# follower_2015-3.net
KiCad netlist of a schematic drawn in EAGLE
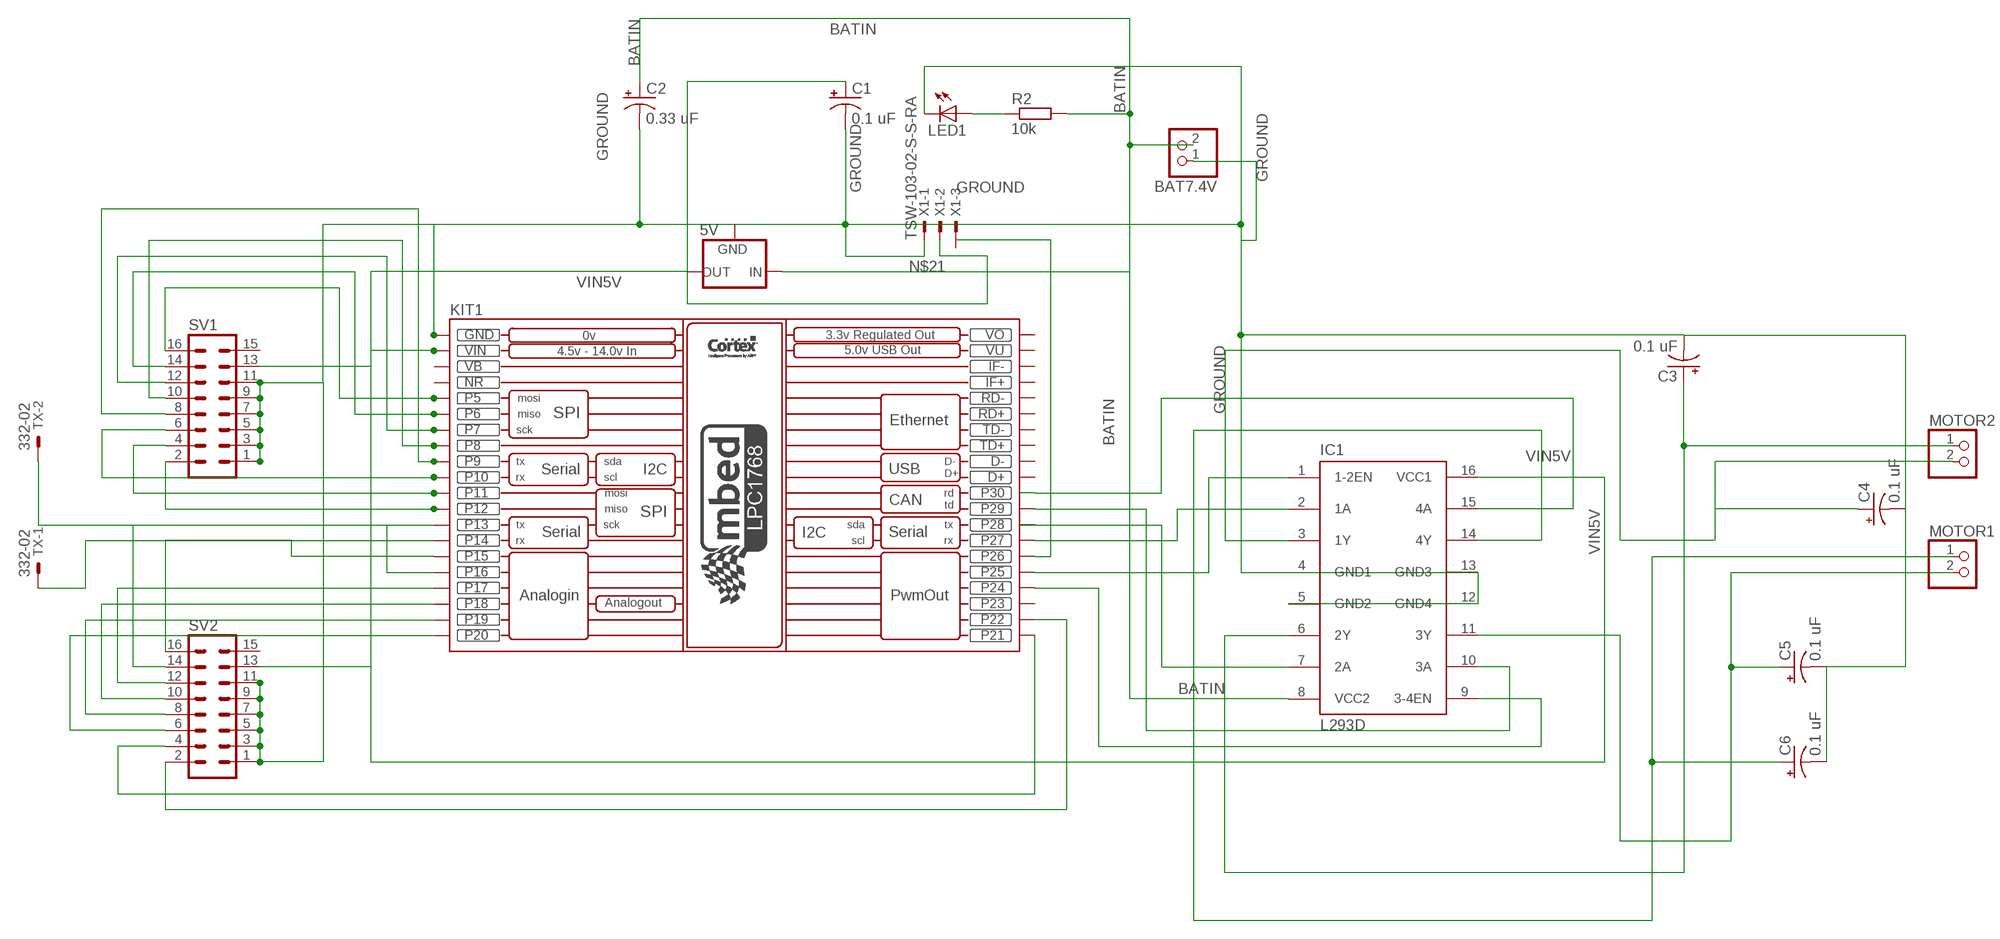
[diagram p0: schematic, sheet 1]

(export (version "E")
  (design (tool "Eeschema 10.0.6"))
  (components
    (comp (ref "5V")
      (value "78XXL")
      (footprint "eagle-import:78XXL")
      (libsource (lib "eagle-import") (part "78XXL"))
    )
    (comp (ref "BAT7.4V")
      (value "PINHD-1X2")
      (footprint "eagle-import:1X02")
      (libsource (lib "eagle-import") (part "PINHD-1X2"))
    )
    (comp (ref "C1")
      (value "0.1 uF")
      (footprint "eagle-import:TT5D6")
      (libsource (lib "eagle-import") (part "CPOL-USTT6D6"))
    )
    (comp (ref "C2")
      (value "0.33 uF")
      (footprint "eagle-import:TT5D6")
      (libsource (lib "eagle-import") (part "CPOL-USTT6D6"))
    )
    (comp (ref "C3")
      (value "0.1 uF")
      (footprint "eagle-import:TT5D6")
      (libsource (lib "eagle-import") (part "CPOL-USTT6D6"))
    )
    (comp (ref "C4")
      (value "0.1 uF")
      (footprint "eagle-import:TT5D6")
      (libsource (lib "eagle-import") (part "CPOL-USTT6D6"))
    )
    (comp (ref "C5")
      (value "0.1 uF")
      (footprint "eagle-import:TT5D6")
      (libsource (lib "eagle-import") (part "CPOL-USTT6D6"))
    )
    (comp (ref "C6")
      (value "0.1 uF")
      (footprint "eagle-import:TT5D6")
      (libsource (lib "eagle-import") (part "CPOL-USTT6D6"))
    )
    (comp (ref "IC1")
      (value "L293D")
      (footprint "eagle-import:DIL16")
      (libsource (lib "eagle-import") (part "L293D"))
    )
    (comp (ref "KIT1")
      (value "MBED_NXP_LPC1768")
      (footprint "eagle-import:MBED-KIT")
      (libsource (lib "eagle-import") (part "MBED_NXP_LPC1768"))
    )
    (comp (ref "LED1")
      (value "LED3MM")
      (footprint "eagle-import:LED3MM")
      (libsource (lib "eagle-import") (part "LED3MM"))
    )
    (comp (ref "MOTOR1")
      (value "PINHD-1X2")
      (footprint "eagle-import:1X02")
      (libsource (lib "eagle-import") (part "PINHD-1X2"))
    )
    (comp (ref "MOTOR2")
      (value "PINHD-1X2")
      (footprint "eagle-import:1X02")
      (libsource (lib "eagle-import") (part "PINHD-1X2"))
    )
    (comp (ref "R2")
      (value "10k")
      (footprint "eagle-import:0204_5")
      (libsource (lib "eagle-import") (part "R-EU_0204/5"))
    )
    (comp (ref "SV1")
      (value "MA08-2")
      (footprint "eagle-import:MA08-2")
      (libsource (lib "eagle-import") (part "MA08-2"))
    )
    (comp (ref "SV2")
      (value "MA08-2")
      (footprint "eagle-import:MA08-2")
      (libsource (lib "eagle-import") (part "MA08-2"))
    )
    (comp (ref "TX")
      (value "332-02")
      (footprint "eagle-import:332-02")
      (libsource (lib "eagle-import") (part "332-02"))
    )
    (comp (ref "X1")
      (value "TSW-103-02-S-S-RA")
      (footprint "eagle-import:TSW-103-02-S-S-RA")
      (libsource (lib "eagle-import") (part "TSW-103-02-S-S-RA"))
    )
  )
  (nets
    (net (code "1") (name "/BATIN") (class "Default")
      (node (ref "BAT7.4V") (pin "2") (pinfunction "2_2") (pintype "passive"))
      (node (ref "C2") (pin "+") (pinfunction "+_+") (pintype "passive"))
      (node (ref "IC1") (pin "8") (pinfunction "VCC2_8") (pintype "power_in"))
      (node (ref "R2") (pin "2") (pinfunction "2_2") (pintype "passive"))
    )
    (net (code "2") (name "/GROUND") (class "Default")
      (node (ref "5V") (pin "GND") (pinfunction "GND_GND") (pintype "input"))
      (node (ref "BAT7.4V") (pin "1") (pinfunction "1_1") (pintype "passive"))
      (node (ref "C1") (pin "-") (pinfunction "-_-") (pintype "passive"))
      (node (ref "C2") (pin "-") (pinfunction "-_-") (pintype "passive"))
      (node (ref "C3") (pin "-") (pinfunction "-_-") (pintype "passive"))
      (node (ref "C4") (pin "-") (pinfunction "-_-") (pintype "passive"))
      (node (ref "C5") (pin "-") (pinfunction "-_-") (pintype "passive"))
      (node (ref "C6") (pin "-") (pinfunction "-_-") (pintype "passive"))
      (node (ref "IC1") (pin "12") (pinfunction "GND4_12") (pintype "power_in"))
      (node (ref "IC1") (pin "13") (pinfunction "GND3_13") (pintype "power_in"))
      (node (ref "IC1") (pin "4") (pinfunction "GND1_4") (pintype "power_in"))
      (node (ref "IC1") (pin "5") (pinfunction "GND2_5") (pintype "power_in"))
      (node (ref "KIT1") (pin "GND") (pinfunction "GND_GND") (pintype "power_in"))
      (node (ref "LED1") (pin "K") (pinfunction "C_K") (pintype "passive"))
      (node (ref "SV1") (pin "1") (pinfunction "1_1") (pintype "passive"))
      (node (ref "SV1") (pin "11") (pinfunction "11_11") (pintype "passive"))
      (node (ref "SV1") (pin "3") (pinfunction "3_3") (pintype "passive"))
      (node (ref "SV1") (pin "5") (pinfunction "5_5") (pintype "passive"))
      (node (ref "SV1") (pin "7") (pinfunction "7_7") (pintype "passive"))
      (node (ref "SV1") (pin "9") (pinfunction "9_9") (pintype "passive"))
      (node (ref "SV2") (pin "1") (pinfunction "1_1") (pintype "passive"))
      (node (ref "SV2") (pin "11") (pinfunction "11_11") (pintype "passive"))
      (node (ref "SV2") (pin "3") (pinfunction "3_3") (pintype "passive"))
      (node (ref "SV2") (pin "5") (pinfunction "5_5") (pintype "passive"))
      (node (ref "SV2") (pin "7") (pinfunction "7_7") (pintype "passive"))
      (node (ref "SV2") (pin "9") (pinfunction "9_9") (pintype "passive"))
    )
    (net (code "3") (name "/N$21") (class "Default")
      (node (ref "5V") (pin "IN") (pinfunction "IN_IN") (pintype "input"))
    )
    (net (code "4") (name "/NR") (class "Default")
      (node (ref "KIT1") (pin "NR") (pinfunction "NR_NR") (pintype "power_in"))
    )
    (net (code "5") (name "/VB") (class "Default")
      (node (ref "KIT1") (pin "VB") (pinfunction "VB_VB") (pintype "power_in"))
    )
    (net (code "6") (name "/VIN5V") (class "Default")
      (node (ref "5V") (pin "OUT") (pinfunction "OUT_OUT") (pintype "passive"))
      (node (ref "C1") (pin "+") (pinfunction "+_+") (pintype "passive"))
      (node (ref "IC1") (pin "16") (pinfunction "VCC1_16") (pintype "power_in"))
      (node (ref "KIT1") (pin "VIN") (pinfunction "VIN_VIN") (pintype "power_in"))
      (node (ref "SV1") (pin "13") (pinfunction "13_13") (pintype "passive"))
      (node (ref "SV2") (pin "13") (pinfunction "13_13") (pintype "passive"))
    )
    (net (code "7") (name "/VO") (class "Default")
      (node (ref "KIT1") (pin "VOUT") (pinfunction "VO_VOUT") (pintype "power_in"))
    )
    (net (code "8") (name "/VU") (class "Default")
      (node (ref "KIT1") (pin "VU") (pinfunction "VU_VU") (pintype "power_in"))
    )
    (net (code "9") (name "Net-(IC1-1-2EN)") (class "Default")
      (node (ref "IC1") (pin "1") (pinfunction "1-2EN_1") (pintype "input"))
      (node (ref "KIT1") (pin "P$25") (pinfunction "P25_P$25") (pintype "bidirectional"))
    )
    (net (code "10") (name "Net-(IC1-1A)") (class "Default")
      (node (ref "IC1") (pin "2") (pinfunction "1A_2") (pintype "input"))
      (node (ref "KIT1") (pin "P$27") (pinfunction "P27_P$27") (pintype "bidirectional"))
    )
    (net (code "11") (name "Net-(IC1-1Y)") (class "Default")
      (node (ref "C4") (pin "+") (pinfunction "+_+") (pintype "passive"))
      (node (ref "IC1") (pin "3") (pinfunction "1Y_3") (pintype "output"))
      (node (ref "MOTOR2") (pin "2") (pinfunction "2_2") (pintype "passive"))
    )
    (net (code "12") (name "Net-(IC1-2Y)") (class "Default")
      (node (ref "C3") (pin "+") (pinfunction "+_+") (pintype "passive"))
      (node (ref "IC1") (pin "6") (pinfunction "2Y_6") (pintype "output"))
      (node (ref "MOTOR2") (pin "1") (pinfunction "1_1") (pintype "passive"))
    )
    (net (code "13") (name "Net-(IC1-3-4EN)") (class "Default")
      (node (ref "IC1") (pin "9") (pinfunction "3-4EN_9") (pintype "input"))
      (node (ref "KIT1") (pin "P$24") (pinfunction "P24_P$24") (pintype "bidirectional"))
    )
    (net (code "14") (name "Net-(IC1-3A)") (class "Default")
      (node (ref "IC1") (pin "10") (pinfunction "3A_10") (pintype "input"))
      (node (ref "KIT1") (pin "P$29") (pinfunction "P29_P$29") (pintype "bidirectional"))
    )
    (net (code "15") (name "Net-(IC1-3Y)") (class "Default")
      (node (ref "C5") (pin "+") (pinfunction "+_+") (pintype "passive"))
      (node (ref "IC1") (pin "11") (pinfunction "3Y_11") (pintype "output"))
      (node (ref "MOTOR1") (pin "2") (pinfunction "2_2") (pintype "passive"))
    )
    (net (code "16") (name "Net-(IC1-4A)") (class "Default")
      (node (ref "IC1") (pin "15") (pinfunction "4A_15") (pintype "input"))
      (node (ref "KIT1") (pin "P$30") (pinfunction "P30_P$30") (pintype "bidirectional"))
    )
    (net (code "17") (name "Net-(IC1-4Y)") (class "Default")
      (node (ref "C6") (pin "+") (pinfunction "+_+") (pintype "passive"))
      (node (ref "IC1") (pin "14") (pinfunction "4Y_14") (pintype "output"))
      (node (ref "MOTOR1") (pin "1") (pinfunction "1_1") (pintype "passive"))
    )
    (net (code "18") (name "Net-(KIT1-P5)") (class "Default")
      (node (ref "KIT1") (pin "P$5") (pinfunction "P5_P$5") (pintype "bidirectional"))
      (node (ref "SV1") (pin "16") (pinfunction "16_16") (pintype "passive"))
    )
    (net (code "19") (name "Net-(KIT1-P6)") (class "Default")
      (node (ref "KIT1") (pin "P$6") (pinfunction "P6_P$6") (pintype "bidirectional"))
      (node (ref "SV1") (pin "14") (pinfunction "14_14") (pintype "passive"))
    )
    (net (code "20") (name "Net-(KIT1-P7)") (class "Default")
      (node (ref "KIT1") (pin "P$7") (pinfunction "P7_P$7") (pintype "bidirectional"))
      (node (ref "SV1") (pin "12") (pinfunction "12_12") (pintype "passive"))
    )
    (net (code "21") (name "Net-(KIT1-P8)") (class "Default")
      (node (ref "KIT1") (pin "P$8") (pinfunction "P8_P$8") (pintype "bidirectional"))
      (node (ref "SV1") (pin "10") (pinfunction "10_10") (pintype "passive"))
    )
    (net (code "22") (name "Net-(KIT1-P9)") (class "Default")
      (node (ref "KIT1") (pin "P$9") (pinfunction "P9_P$9") (pintype "bidirectional"))
      (node (ref "SV1") (pin "8") (pinfunction "8_8") (pintype "passive"))
    )
    (net (code "23") (name "Net-(KIT1-P10)") (class "Default")
      (node (ref "KIT1") (pin "P$10") (pinfunction "P10_P$10") (pintype "bidirectional"))
      (node (ref "SV1") (pin "6") (pinfunction "6_6") (pintype "passive"))
    )
    (net (code "24") (name "Net-(KIT1-P11)") (class "Default")
      (node (ref "KIT1") (pin "P$11") (pinfunction "P11_P$11") (pintype "bidirectional"))
      (node (ref "SV1") (pin "4") (pinfunction "4_4") (pintype "passive"))
    )
    (net (code "25") (name "Net-(KIT1-P12)") (class "Default")
      (node (ref "KIT1") (pin "P$12") (pinfunction "P12_P$12") (pintype "bidirectional"))
      (node (ref "SV1") (pin "2") (pinfunction "2_2") (pintype "passive"))
    )
    (net (code "26") (name "Net-(KIT1-P13)") (class "Default")
      (node (ref "KIT1") (pin "P$13") (pinfunction "P13_P$13") (pintype "bidirectional"))
      (node (ref "TX") (pin "2") (pinfunction "S_2") (pintype "passive"))
    )
    (net (code "27") (name "Net-(KIT1-P14)") (class "Default")
      (node (ref "KIT1") (pin "P$14") (pinfunction "P14_P$14") (pintype "bidirectional"))
      (node (ref "TX") (pin "1") (pinfunction "S_1") (pintype "passive"))
    )
    (net (code "28") (name "Net-(KIT1-P15)") (class "Default")
      (node (ref "KIT1") (pin "P$15") (pinfunction "P15_P$15") (pintype "bidirectional"))
      (node (ref "SV2") (pin "16") (pinfunction "16_16") (pintype "passive"))
    )
    (net (code "29") (name "Net-(KIT1-P16)") (class "Default")
      (node (ref "KIT1") (pin "P$16") (pinfunction "P16_P$16") (pintype "bidirectional"))
      (node (ref "SV2") (pin "14") (pinfunction "14_14") (pintype "passive"))
    )
    (net (code "30") (name "Net-(KIT1-P17)") (class "Default")
      (node (ref "KIT1") (pin "P$17") (pinfunction "P17_P$17") (pintype "bidirectional"))
      (node (ref "SV2") (pin "12") (pinfunction "12_12") (pintype "passive"))
    )
    (net (code "31") (name "Net-(KIT1-P18)") (class "Default")
      (node (ref "KIT1") (pin "P$18") (pinfunction "P18_P$18") (pintype "bidirectional"))
      (node (ref "SV2") (pin "10") (pinfunction "10_10") (pintype "passive"))
    )
    (net (code "32") (name "Net-(KIT1-P19)") (class "Default")
      (node (ref "KIT1") (pin "P$19") (pinfunction "P19_P$19") (pintype "bidirectional"))
      (node (ref "SV2") (pin "8") (pinfunction "8_8") (pintype "passive"))
    )
    (net (code "33") (name "Net-(KIT1-P20)") (class "Default")
      (node (ref "KIT1") (pin "P$20") (pinfunction "P20_P$20") (pintype "bidirectional"))
      (node (ref "SV2") (pin "6") (pinfunction "6_6") (pintype "passive"))
    )
    (net (code "34") (name "Net-(KIT1-P21)") (class "Default")
      (node (ref "KIT1") (pin "P$21") (pinfunction "P21_P$21") (pintype "bidirectional"))
      (node (ref "SV2") (pin "4") (pinfunction "4_4") (pintype "passive"))
    )
    (net (code "35") (name "Net-(KIT1-P22)") (class "Default")
      (node (ref "KIT1") (pin "P$22") (pinfunction "P22_P$22") (pintype "bidirectional"))
      (node (ref "SV2") (pin "2") (pinfunction "2_2") (pintype "passive"))
    )
    (net (code "36") (name "Net-(LED1-PadA)") (class "Default")
      (node (ref "LED1") (pin "A") (pinfunction "A_A") (pintype "passive"))
      (node (ref "R2") (pin "1") (pinfunction "1_1") (pintype "passive"))
    )
    (net (code "37") (name "unconnected-(IC1-2A-Pad7)") (class "Default")
      (node (ref "IC1") (pin "7") (pinfunction "2A_7") (pintype "input"))
    )
    (net (code "38") (name "unconnected-(KIT1-P23-PadP$23)") (class "Default")
      (node (ref "KIT1") (pin "P$23") (pinfunction "P23_P$23") (pintype "bidirectional"))
    )
    (net (code "39") (name "unconnected-(KIT1-P26-PadP$26)") (class "Default")
      (node (ref "KIT1") (pin "P$26") (pinfunction "P26_P$26") (pintype "bidirectional"))
    )
    (net (code "40") (name "unconnected-(KIT1-P28-PadP$28)") (class "Default")
      (node (ref "KIT1") (pin "P$28") (pinfunction "P28_P$28") (pintype "bidirectional"))
    )
    (net (code "41") (name "unconnected-(KIT1-PadD+)") (class "Default")
      (node (ref "KIT1") (pin "D+") (pinfunction "D+_D+") (pintype "bidirectional"))
    )
    (net (code "42") (name "unconnected-(KIT1-PadD-)") (class "Default")
      (node (ref "KIT1") (pin "D-") (pinfunction "D-_D-") (pintype "bidirectional"))
    )
    (net (code "43") (name "unconnected-(KIT1-PadIF+)") (class "Default")
      (node (ref "KIT1") (pin "IF+") (pinfunction "IF+_IF+") (pintype "bidirectional"))
    )
    (net (code "44") (name "unconnected-(KIT1-PadIF-)") (class "Default")
      (node (ref "KIT1") (pin "IF-") (pinfunction "IF-_IF-") (pintype "bidirectional"))
    )
    (net (code "45") (name "unconnected-(KIT1-PadRD+)") (class "Default")
      (node (ref "KIT1") (pin "RD+") (pinfunction "RD+_RD+") (pintype "bidirectional"))
    )
    (net (code "46") (name "unconnected-(KIT1-PadRD-)") (class "Default")
      (node (ref "KIT1") (pin "RD-") (pinfunction "RD-_RD-") (pintype "bidirectional"))
    )
    (net (code "47") (name "unconnected-(KIT1-PadTD+)") (class "Default")
      (node (ref "KIT1") (pin "TD+") (pinfunction "TD+_TD+") (pintype "bidirectional"))
    )
    (net (code "48") (name "unconnected-(KIT1-PadTD-)") (class "Default")
      (node (ref "KIT1") (pin "TD-") (pinfunction "TD-_TD-") (pintype "bidirectional"))
    )
    (net (code "49") (name "unconnected-(SV1-Pad15)") (class "Default")
      (node (ref "SV1") (pin "15") (pinfunction "15_15") (pintype "passive"))
    )
    (net (code "50") (name "unconnected-(SV2-Pad15)") (class "Default")
      (node (ref "SV2") (pin "15") (pinfunction "15_15") (pintype "passive"))
    )
    (net (code "51") (name "unconnected-(X1-Pad1)") (class "Default")
      (node (ref "X1") (pin "1") (pinfunction "1_1") (pintype "passive"))
    )
    (net (code "52") (name "unconnected-(X1B-1-Pad2)") (class "Default")
      (node (ref "X1") (pin "2") (pinfunction "1_2") (pintype "passive"))
    )
    (net (code "53") (name "unconnected-(X1C-1-Pad3)") (class "Default")
      (node (ref "X1") (pin "3") (pinfunction "1_3") (pintype "passive"))
    )
  )
)
